# Programming_USB.net
KiCad netlist of a schematic drawn in Altium Designer
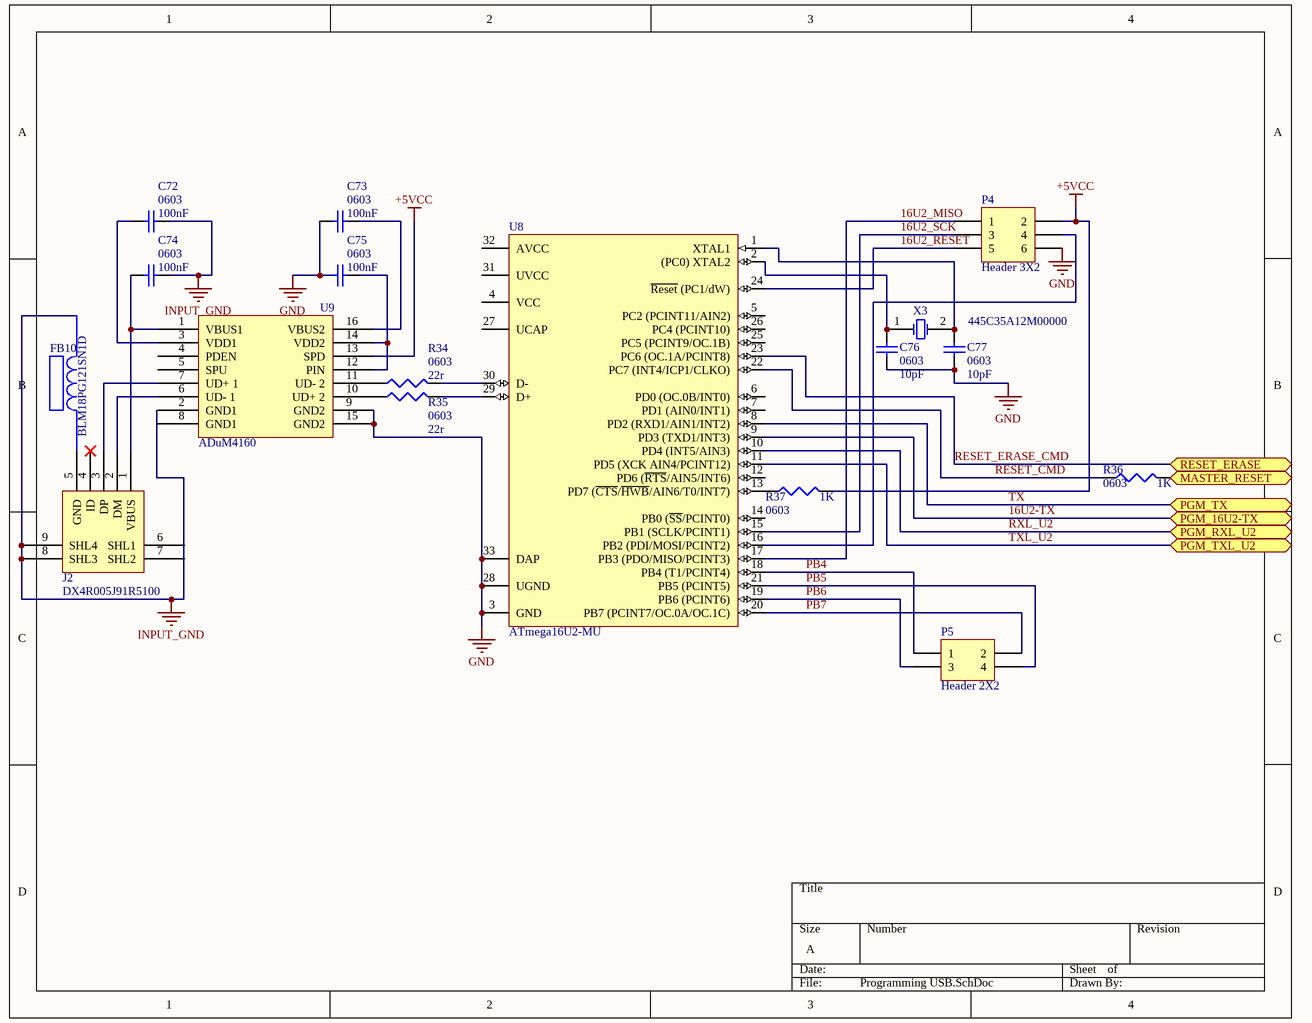
[diagram p0: Programming USB.SchDoc]

(export (version "E")
  (design (tool "Eeschema 10.0.6"))
  (components
    (comp (ref "C72")
      (value "0603")
      (footprint "1608[0603]")
      (description "Capacitor (Semiconductor SIM Model)")
      (fields (field (name "ALTIUM_VALUE") "100nF") (field (name "PUBLISHER") "Altium Limited"))
      (libsource (lib "Miscellaneous Devices") (part "Cap Semi"))
    )
    (comp (ref "C73")
      (value "0603")
      (footprint "1608[0603]")
      (description "Capacitor (Semiconductor SIM Model)")
      (fields (field (name "ALTIUM_VALUE") "100nF") (field (name "PUBLISHER") "Altium Limited"))
      (libsource (lib "Miscellaneous Devices") (part "Cap Semi"))
    )
    (comp (ref "C74")
      (value "0603")
      (footprint "1608[0603]")
      (description "Capacitor (Semiconductor SIM Model)")
      (fields (field (name "ALTIUM_VALUE") "100nF") (field (name "PUBLISHER") "Altium Limited"))
      (libsource (lib "Miscellaneous Devices") (part "Cap Semi"))
    )
    (comp (ref "C75")
      (value "0603")
      (footprint "1608[0603]")
      (description "Capacitor (Semiconductor SIM Model)")
      (fields (field (name "ALTIUM_VALUE") "100nF") (field (name "PUBLISHER") "Altium Limited"))
      (libsource (lib "Miscellaneous Devices") (part "Cap Semi"))
    )
    (comp (ref "C76")
      (value "0603")
      (footprint "1608[0603]")
      (description "Capacitor (Semiconductor SIM Model)")
      (fields (field (name "ALTIUM_VALUE") "10pF") (field (name "PUBLISHER") "Altium Limited"))
      (libsource (lib "Miscellaneous Devices") (part "Cap Semi"))
    )
    (comp (ref "C77")
      (value "0603")
      (footprint "1608[0603]")
      (description "Capacitor (Semiconductor SIM Model)")
      (fields (field (name "ALTIUM_VALUE") "10pF") (field (name "PUBLISHER") "Altium Limited"))
      (libsource (lib "Miscellaneous Devices") (part "Cap Semi"))
    )
    (comp (ref "FB10")
      (value "BLM18PG121SN1D")
      (footprint "BLM18PG121SN1D")
      (libsource (lib "Adams Altium Library") (part "BLM18PG121SN1D"))
    )
    (comp (ref "J2")
      (value "DX4R005J91R5100")
      (footprint "Micro USB Circular Holes Only")
      (description "Micro USB Jack B")
      (libsource (lib "Adams Altium Library") (part "Micro USB"))
    )
    (comp (ref "P4")
      (value "Header 3X2")
      (footprint "HDR2X3")
      (description "Header, 3-Pin, Dual row")
      (fields (field (name "PUBLISHER") "Altium Limited"))
      (libsource (lib "Miscellaneous Connectors") (part "Header 3X2"))
    )
    (comp (ref "P5")
      (value "Header 2X2")
      (footprint "HDR2X2")
      (description "Header, 2-Pin, Dual row")
      (fields (field (name "PUBLISHER") "Altium Limited"))
      (libsource (lib "Miscellaneous Connectors") (part "Header 2X2"))
    )
    (comp (ref "R34")
      (value "0603")
      (footprint "J1-0603")
      (description "Resistor")
      (fields (field (name "ALTIUM_VALUE") "22r") (field (name "PUBLISHER") "Altium Limited"))
      (libsource (lib "Miscellaneous Devices") (part "Res3"))
    )
    (comp (ref "R35")
      (value "0603")
      (footprint "J1-0603")
      (description "Resistor")
      (fields (field (name "ALTIUM_VALUE") "22r") (field (name "PUBLISHER") "Altium Limited"))
      (libsource (lib "Miscellaneous Devices") (part "Res3"))
    )
    (comp (ref "R36")
      (value "0603")
      (footprint "J1-0603")
      (description "Resistor")
      (fields (field (name "ALTIUM_VALUE") "1K") (field (name "PUBLISHER") "Altium Limited"))
      (libsource (lib "Miscellaneous Devices") (part "Res3"))
    )
    (comp (ref "R37")
      (value "0603")
      (footprint "J1-0603")
      (description "Resistor")
      (fields (field (name "ALTIUM_VALUE") "1K") (field (name "PUBLISHER") "Altium Limited"))
      (libsource (lib "Miscellaneous Devices") (part "Res3"))
    )
    (comp (ref "U8")
      (value "ATmega16U2-MU")
      (footprint "32PG_L")
      (libsource (lib "Atmel Microcontroller megaAVR") (part "ATmega16U2-MU"))
    )
    (comp (ref "U9")
      (value "ADuM4160")
      (footprint "ADuM4160")
      (description "USB Opto Isolator")
      (libsource (lib "ZMBo Schematic Library") (part "ADuM4160"))
    )
    (comp (ref "X3")
      (value "445C35A12M00000")
      (footprint "R38")
      (description "Crystal Oscillator")
      (fields (field (name "PUBLISHER") "Altium Limited"))
      (libsource (lib "Miscellaneous Devices") (part "XTAL"))
    )
  )
  (nets
    (net (code "1") (name "+5VCC") (class "Default")
      (node (ref "P4") (pin "2") (pinfunction "2_2") (pintype "passive"))
      (node (ref "R37") (pin "2") (pinfunction "2_2") (pintype "passive"))
      (node (ref "U9") (pin "13") (pinfunction "SPD_13") (pintype "passive"))
    )
    (net (code "2") (name "/16U2-TX") (class "Default")
      (node (ref "U8") (pin "9") (pinfunction "PD3_(TXD1/INT3)_9") (pintype "bidirectional"))
    )
    (net (code "3") (name "/16U2_MISO") (class "Default")
      (node (ref "P4") (pin "1") (pinfunction "1_1") (pintype "passive"))
      (node (ref "U8") (pin "17") (pinfunction "PB3_(PDO/MISO/PCINT3)_17") (pintype "bidirectional"))
    )
    (net (code "4") (name "/16U2_RESET") (class "Default")
      (node (ref "P4") (pin "5") (pinfunction "5_5") (pintype "passive"))
      (node (ref "U8") (pin "24") (pinfunction "~{Reset}_(PC1/dW)_24") (pintype "bidirectional"))
    )
    (net (code "5") (name "/16U2_SCK") (class "Default")
      (node (ref "P4") (pin "3") (pinfunction "3_3") (pintype "passive"))
      (node (ref "U8") (pin "15") (pinfunction "PB1_(SCLK/PCINT1)_15") (pintype "bidirectional"))
    )
    (net (code "6") (name "/MASTER_RESET") (class "Default")
      (node (ref "R36") (pin "2") (pinfunction "2_2") (pintype "passive"))
    )
    (net (code "7") (name "/PB4") (class "Default")
      (node (ref "P5") (pin "1") (pinfunction "1_1") (pintype "passive"))
      (node (ref "U8") (pin "18") (pinfunction "PB4_(T1/PCINT4)_18") (pintype "bidirectional"))
    )
    (net (code "8") (name "/PB5") (class "Default")
      (node (ref "P5") (pin "4") (pinfunction "4_4") (pintype "passive"))
      (node (ref "U8") (pin "21") (pinfunction "PB5_(PCINT5)_21") (pintype "bidirectional"))
    )
    (net (code "9") (name "/PB6") (class "Default")
      (node (ref "P5") (pin "3") (pinfunction "3_3") (pintype "passive"))
      (node (ref "U8") (pin "19") (pinfunction "PB6_(PCINT6)_19") (pintype "bidirectional"))
    )
    (net (code "10") (name "/PB7") (class "Default")
      (node (ref "P5") (pin "2") (pinfunction "2_2") (pintype "passive"))
      (node (ref "U8") (pin "20") (pinfunction "PB7_(PCINT7/OC.0A/OC.1C)_20") (pintype "bidirectional"))
    )
    (net (code "11") (name "/RESET_CMD") (class "Default")
      (node (ref "R36") (pin "1") (pinfunction "1_1") (pintype "passive"))
      (node (ref "U8") (pin "22") (pinfunction "PC7_(INT4/ICP1/CLKO)_22") (pintype "bidirectional"))
    )
    (net (code "12") (name "/RESET_ERASE_CMD") (class "Default")
      (node (ref "U8") (pin "23") (pinfunction "PC6_(OC.1A/PCINT8)_23") (pintype "bidirectional"))
    )
    (net (code "13") (name "/RXL_U2") (class "Default")
      (node (ref "U8") (pin "10") (pinfunction "PD4_(INT5/AIN3)_10") (pintype "bidirectional"))
    )
    (net (code "14") (name "/TX") (class "Default")
      (node (ref "U8") (pin "8") (pinfunction "PD2_(RXD1/AIN1/INT2)_8") (pintype "bidirectional"))
    )
    (net (code "15") (name "/TXL_U2") (class "Default")
      (node (ref "U8") (pin "11") (pinfunction "PD5_(XCK_AIN4/PCINT12)_11") (pintype "bidirectional"))
    )
    (net (code "16") (name "GND") (class "Default")
      (node (ref "C73") (pin "2") (pinfunction "2_2") (pintype "passive"))
      (node (ref "C75") (pin "2") (pinfunction "2_2") (pintype "passive"))
      (node (ref "C76") (pin "1") (pinfunction "1_1") (pintype "passive"))
      (node (ref "C77") (pin "1") (pinfunction "1_1") (pintype "passive"))
      (node (ref "P4") (pin "6") (pinfunction "6_6") (pintype "passive"))
      (node (ref "U8") (pin "28") (pinfunction "UGND_28") (pintype "power_in"))
      (node (ref "U8") (pin "3") (pinfunction "GND_3") (pintype "power_in"))
      (node (ref "U8") (pin "33") (pinfunction "DAP_33") (pintype "power_in"))
      (node (ref "U9") (pin "15") (pinfunction "GND2_15") (pintype "passive"))
      (node (ref "U9") (pin "9") (pinfunction "GND2_9") (pintype "passive"))
    )
    (net (code "17") (name "INPUT_GND") (class "Default")
      (node (ref "C72") (pin "1") (pinfunction "1_1") (pintype "passive"))
      (node (ref "C74") (pin "1") (pinfunction "1_1") (pintype "passive"))
      (node (ref "FB10") (pin "2") (pinfunction "2_2") (pintype "passive"))
      (node (ref "J2") (pin "8") (pinfunction "SHL3_8") (pintype "passive"))
      (node (ref "J2") (pin "9") (pinfunction "SHL4_9") (pintype "passive"))
    )
    (net (code "18") (name "Net-(J2-DM)") (class "Default")
      (node (ref "J2") (pin "2") (pinfunction "DM_2") (pintype "passive"))
      (node (ref "U9") (pin "6") (pinfunction "UD-_1_6") (pintype "passive"))
    )
    (net (code "19") (name "Net-(J2-DP)") (class "Default")
      (node (ref "J2") (pin "3") (pinfunction "DP_3") (pintype "passive"))
      (node (ref "U9") (pin "7") (pinfunction "UD+_1_7") (pintype "passive"))
    )
    (net (code "20") (name "Net-(J2-GND)") (class "Default")
      (node (ref "FB10") (pin "1") (pinfunction "1_1") (pintype "passive"))
      (node (ref "J2") (pin "5") (pinfunction "GND_5") (pintype "passive"))
    )
    (net (code "21") (name "Net-(J2-VBUS)") (class "Default")
      (node (ref "C74") (pin "2") (pinfunction "2_2") (pintype "passive"))
      (node (ref "J2") (pin "1") (pinfunction "VBUS_1") (pintype "passive"))
      (node (ref "U9") (pin "1") (pinfunction "VBUS1_1") (pintype "passive"))
    )
    (net (code "22") (name "Net-(U8-(PC0)_XTAL2)") (class "Default")
      (node (ref "C76") (pin "2") (pinfunction "2_2") (pintype "passive"))
      (node (ref "U8") (pin "2") (pinfunction "(PC0)_XTAL2_2") (pintype "bidirectional"))
      (node (ref "X3") (pin "1") (pinfunction "OSC1_1") (pintype "passive"))
    )
    (net (code "23") (name "Net-(U8-D+)") (class "Default")
      (node (ref "R35") (pin "2") (pinfunction "2_2") (pintype "passive"))
      (node (ref "U8") (pin "29") (pinfunction "D+_29") (pintype "bidirectional"))
    )
    (net (code "24") (name "Net-(U8-D-)") (class "Default")
      (node (ref "R34") (pin "2") (pinfunction "2_2") (pintype "passive"))
      (node (ref "U8") (pin "30") (pinfunction "D-_30") (pintype "bidirectional"))
    )
    (net (code "25") (name "Net-(U8-PB2_(PDI{slash}MOSI{slash}PCINT2))") (class "Default")
      (node (ref "P4") (pin "4") (pinfunction "4_4") (pintype "passive"))
      (node (ref "U8") (pin "16") (pinfunction "PB2_(PDI/MOSI/PCINT2)_16") (pintype "bidirectional"))
    )
    (net (code "26") (name "Net-(U8-PD7_(~{CTS}{slash}~{HWB}{slash}AIN6{slash}T0{slash}INT7))") (class "Default")
      (node (ref "R37") (pin "1") (pinfunction "1_1") (pintype "passive"))
      (node (ref "U8") (pin "13") (pinfunction "PD7_(~{CTS}/~{HWB}/AIN6/T0/INT7)_13") (pintype "bidirectional"))
    )
    (net (code "27") (name "Net-(U8-XTAL1)") (class "Default")
      (node (ref "C77") (pin "2") (pinfunction "2_2") (pintype "passive"))
      (node (ref "U8") (pin "1") (pinfunction "XTAL1_1") (pintype "input"))
      (node (ref "X3") (pin "2") (pinfunction "OSC2_2") (pintype "passive"))
    )
    (net (code "28") (name "Net-(U9-PIN)") (class "Default")
      (node (ref "C75") (pin "1") (pinfunction "1_1") (pintype "passive"))
      (node (ref "U9") (pin "12") (pinfunction "PIN_12") (pintype "passive"))
      (node (ref "U9") (pin "14") (pinfunction "VDD2_14") (pintype "passive"))
    )
    (net (code "29") (name "Net-(U9-UD+_2)") (class "Default")
      (node (ref "R35") (pin "1") (pinfunction "1_1") (pintype "passive"))
      (node (ref "U9") (pin "10") (pinfunction "UD+_2_10") (pintype "passive"))
    )
    (net (code "30") (name "Net-(U9-UD-_2)") (class "Default")
      (node (ref "R34") (pin "1") (pinfunction "1_1") (pintype "passive"))
      (node (ref "U9") (pin "11") (pinfunction "UD-_2_11") (pintype "passive"))
    )
    (net (code "31") (name "Net-(U9-VBUS2)") (class "Default")
      (node (ref "C73") (pin "1") (pinfunction "1_1") (pintype "passive"))
      (node (ref "U9") (pin "16") (pinfunction "VBUS2_16") (pintype "passive"))
    )
    (net (code "32") (name "Net-(U9-VDD1)") (class "Default")
      (node (ref "C72") (pin "2") (pinfunction "2_2") (pintype "passive"))
      (node (ref "U9") (pin "3") (pinfunction "VDD1_3") (pintype "passive"))
    )
    (net (code "33") (name "unconnected-(J2-ID-Pad4)") (class "Default")
      (node (ref "J2") (pin "4") (pinfunction "ID_4") (pintype "passive+no_connect"))
    )
    (net (code "34") (name "unconnected-(J2-SHL1-Pad6)") (class "Default")
      (node (ref "J2") (pin "6") (pinfunction "SHL1_6") (pintype "passive"))
    )
    (net (code "35") (name "unconnected-(J2-SHL2-Pad7)") (class "Default")
      (node (ref "J2") (pin "7") (pinfunction "SHL2_7") (pintype "passive"))
    )
    (net (code "36") (name "unconnected-(U8-AVCC-Pad32)") (class "Default")
      (node (ref "U8") (pin "32") (pinfunction "AVCC_32") (pintype "power_in"))
    )
    (net (code "37") (name "unconnected-(U8-PB0_(~{SS}{slash}PCINT0)-Pad14)") (class "Default")
      (node (ref "U8") (pin "14") (pinfunction "PB0_(~{SS}/PCINT0)_14") (pintype "bidirectional"))
    )
    (net (code "38") (name "unconnected-(U8-PC2_(PCINT11{slash}AIN2)-Pad5)") (class "Default")
      (node (ref "U8") (pin "5") (pinfunction "PC2_(PCINT11/AIN2)_5") (pintype "bidirectional"))
    )
    (net (code "39") (name "unconnected-(U8-PC4_(PCINT10)-Pad26)") (class "Default")
      (node (ref "U8") (pin "26") (pinfunction "PC4_(PCINT10)_26") (pintype "bidirectional"))
    )
    (net (code "40") (name "unconnected-(U8-PC5_(PCINT9{slash}OC.1B)-Pad25)") (class "Default")
      (node (ref "U8") (pin "25") (pinfunction "PC5_(PCINT9/OC.1B)_25") (pintype "bidirectional"))
    )
    (net (code "41") (name "unconnected-(U8-PD0_(OC.0B{slash}INT0)-Pad6)") (class "Default")
      (node (ref "U8") (pin "6") (pinfunction "PD0_(OC.0B/INT0)_6") (pintype "bidirectional"))
    )
    (net (code "42") (name "unconnected-(U8-PD1_(AIN0{slash}INT1)-Pad7)") (class "Default")
      (node (ref "U8") (pin "7") (pinfunction "PD1_(AIN0/INT1)_7") (pintype "bidirectional"))
    )
    (net (code "43") (name "unconnected-(U8-PD6_(~{RTS}{slash}AIN5{slash}INT6)-Pad12)") (class "Default")
      (node (ref "U8") (pin "12") (pinfunction "PD6_(~{RTS}/AIN5/INT6)_12") (pintype "bidirectional"))
    )
    (net (code "44") (name "unconnected-(U8-UCAP-Pad27)") (class "Default")
      (node (ref "U8") (pin "27") (pinfunction "UCAP_27") (pintype "power_in"))
    )
    (net (code "45") (name "unconnected-(U8-UVCC-Pad31)") (class "Default")
      (node (ref "U8") (pin "31") (pinfunction "UVCC_31") (pintype "power_in"))
    )
    (net (code "46") (name "unconnected-(U8-VCC-Pad4)") (class "Default")
      (node (ref "U8") (pin "4") (pinfunction "VCC_4") (pintype "power_in"))
    )
    (net (code "47") (name "unconnected-(U9-GND1-Pad2)") (class "Default")
      (node (ref "U9") (pin "2") (pinfunction "GND1_2") (pintype "passive"))
    )
    (net (code "48") (name "unconnected-(U9-GND1-Pad8)") (class "Default")
      (node (ref "U9") (pin "8") (pinfunction "GND1_8") (pintype "passive"))
    )
    (net (code "49") (name "unconnected-(U9-PDEN-Pad4)") (class "Default")
      (node (ref "U9") (pin "4") (pinfunction "PDEN_4") (pintype "passive"))
    )
    (net (code "50") (name "unconnected-(U9-SPU-Pad5)") (class "Default")
      (node (ref "U9") (pin "5") (pinfunction "SPU_5") (pintype "passive"))
    )
  )
)
